# esp_altimeter_evo2.net
KiCad netlist of a schematic drawn in Altium Designer
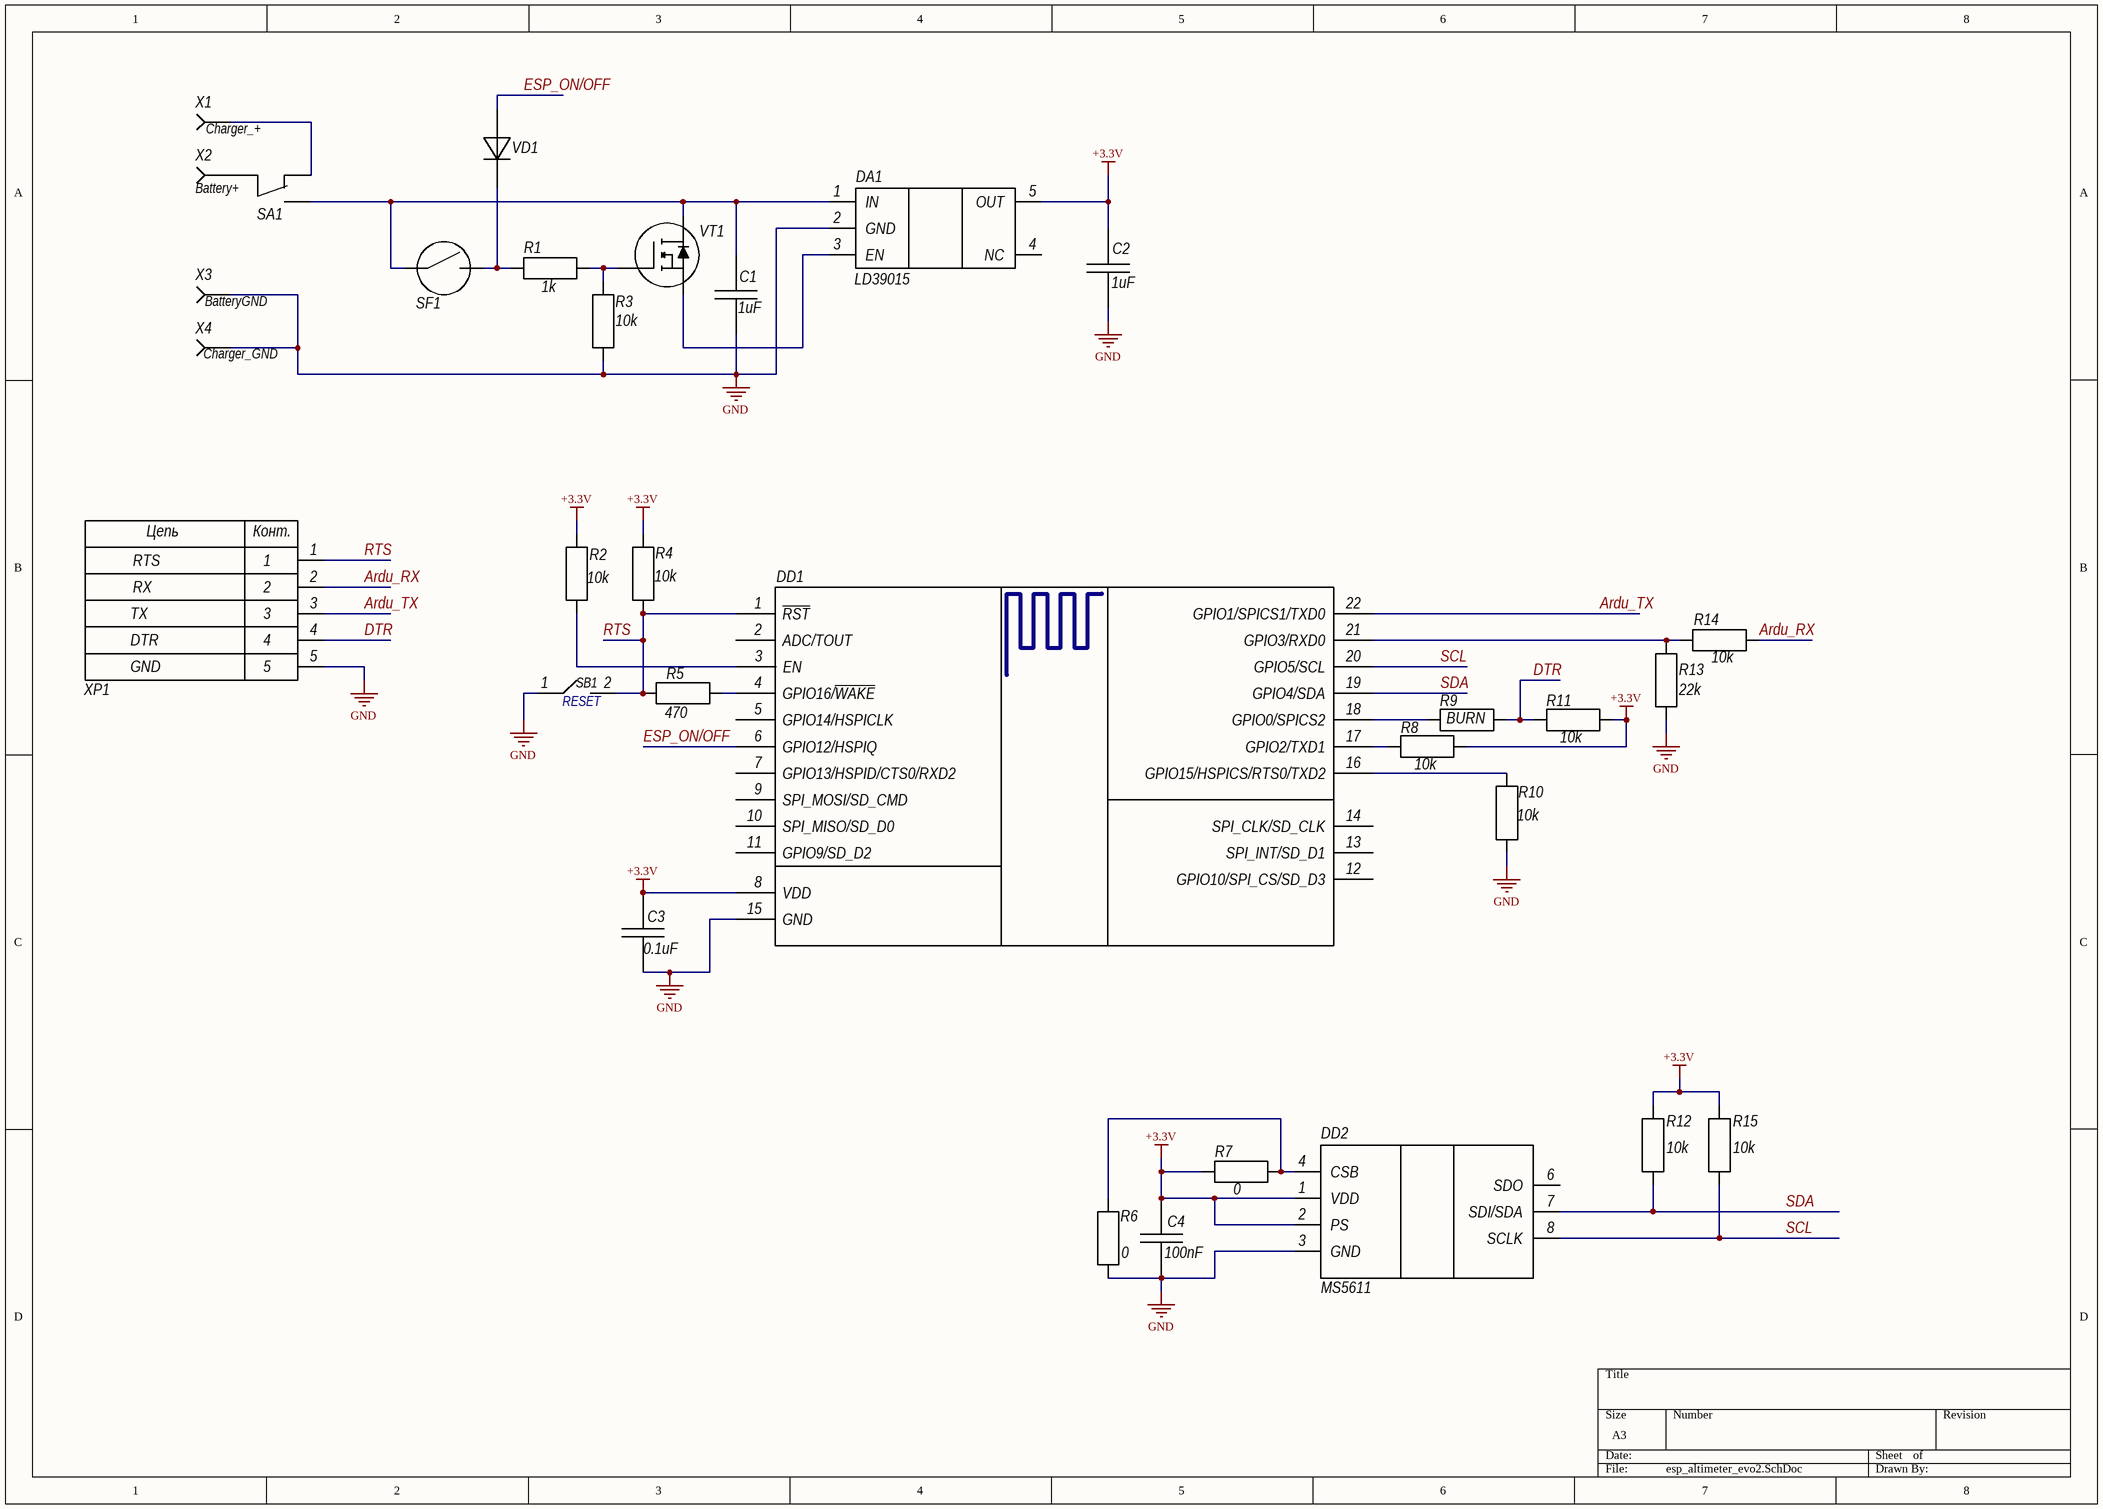
[diagram p0: esp_altimeter_evo2.SchDoc]

(export (version "E")
  (design (tool "Eeschema 10.0.6"))
  (components
    (comp (ref "C1")
      (value "1uF")
      (footprint "CAP EIA 0603")
      (fields (field (name "Comment") "Cap EIA 0603"))
      (libsource (lib "Altium_Capicators_Lib") (part "Cap EIA 0603"))
    )
    (comp (ref "C2")
      (value "1uF")
      (footprint "CAP EIA 0603")
      (fields (field (name "Comment") "Cap EIA 0603"))
      (libsource (lib "Altium_Capicators_Lib") (part "Cap EIA 0603"))
    )
    (comp (ref "C3")
      (value "0.1uF")
      (footprint "CAP EIA 0603")
      (fields (field (name "Comment") "Cap EIA 0603"))
      (libsource (lib "Altium_Capicators_Lib") (part "Cap EIA 0603"))
    )
    (comp (ref "C4")
      (value "100nF")
      (footprint "CAP EIA 0603")
      (fields (field (name "Comment") "Cap EIA 0603"))
      (libsource (lib "Altium_Capicators_Lib") (part "Cap EIA 0603"))
    )
    (comp (ref "DA1")
      (value "LD39015")
      (footprint "SOT23-5L")
      (libsource (lib "Altium_Power_System_Lib") (part "LD39015"))
    )
    (comp (ref "DD1")
      (value "ESP8266 ESP-12E-RU")
      (footprint "ESP8266 ESP-12-E")
      (fields (field (name "MANUFACTURER") "Espressif"))
      (libsource (lib "Altium_Microcontrollers_Lib") (part "ESP8266 ESP-12E-RU"))
    )
    (comp (ref "DD2")
      (value "MS5611")
      (footprint "MS5611")
      (libsource (lib "Altium_Sensors_Lib") (part "MS5611"))
    )
    (comp (ref "R1")
      (value "1k")
      (footprint "RES EIA 0603")
      (fields (field (name "Comment") "Res EIA 0603"))
      (libsource (lib "Altium_Resistors_Lib") (part "Res EIA 0603"))
    )
    (comp (ref "R2")
      (value "10k")
      (footprint "RES EIA 0603")
      (fields (field (name "Comment") "Res EIA 0603"))
      (libsource (lib "Altium_Resistors_Lib") (part "Res EIA 0603"))
    )
    (comp (ref "R3")
      (value "10k")
      (footprint "RES EIA 0603")
      (fields (field (name "Comment") "Res EIA 0603"))
      (libsource (lib "Altium_Resistors_Lib") (part "Res EIA 0603"))
    )
    (comp (ref "R4")
      (value "10k")
      (footprint "RES EIA 0603")
      (fields (field (name "Comment") "Res EIA 0603"))
      (libsource (lib "Altium_Resistors_Lib") (part "Res EIA 0603"))
    )
    (comp (ref "R5")
      (value "470")
      (footprint "RES EIA 0603")
      (fields (field (name "Comment") "Res EIA 0603"))
      (libsource (lib "Altium_Resistors_Lib") (part "Res EIA 0603"))
    )
    (comp (ref "R6")
      (value "0")
      (footprint "RES EIA 0402")
      (fields (field (name "Comment") "Res EIA 0402"))
      (libsource (lib "Altium_Resistors_Lib") (part "Res EIA 0402"))
    )
    (comp (ref "R7")
      (value "0")
      (footprint "RES EIA 0402")
      (fields (field (name "Comment") "Res EIA 0402"))
      (libsource (lib "Altium_Resistors_Lib") (part "Res EIA 0402"))
    )
    (comp (ref "R8")
      (value "10k")
      (footprint "RES EIA 0603")
      (fields (field (name "Comment") "Res EIA 0603"))
      (libsource (lib "Altium_Resistors_Lib") (part "Res EIA 0603"))
    )
    (comp (ref "R9")
      (value "Res EIA 0603")
      (footprint "RES EIA 0603")
      (fields (field (name "NAME") "BURN"))
      (libsource (lib "Altium_Resistors_Lib") (part "Res EIA 0603"))
    )
    (comp (ref "R10")
      (value "10k")
      (footprint "RES EIA 0603")
      (fields (field (name "Comment") "Res EIA 0603"))
      (libsource (lib "Altium_Resistors_Lib") (part "Res EIA 0603"))
    )
    (comp (ref "R11")
      (value "10k")
      (footprint "RES EIA 0603")
      (fields (field (name "Comment") "Res EIA 0603"))
      (libsource (lib "Altium_Resistors_Lib") (part "Res EIA 0603"))
    )
    (comp (ref "R12")
      (value "10k")
      (footprint "RES EIA 0603")
      (fields (field (name "Comment") "Res EIA 0603"))
      (libsource (lib "Altium_Resistors_Lib") (part "Res EIA 0603"))
    )
    (comp (ref "R13")
      (value "22k")
      (footprint "RES EIA 0603")
      (fields (field (name "Comment") "Res EIA 0603"))
      (libsource (lib "Altium_Resistors_Lib") (part "Res EIA 0603"))
    )
    (comp (ref "R14")
      (value "10k")
      (footprint "RES EIA 0603")
      (fields (field (name "Comment") "Res EIA 0603"))
      (libsource (lib "Altium_Resistors_Lib") (part "Res EIA 0603"))
    )
    (comp (ref "R15")
      (value "10k")
      (footprint "RES EIA 0603")
      (fields (field (name "Comment") "Res EIA 0603"))
      (libsource (lib "Altium_Resistors_Lib") (part "Res EIA 0603"))
    )
    (comp (ref "SA1")
      (value "IS-1290")
      (footprint "IS-1290F")
      (libsource (lib "Altium_Switchers_Lib") (part "IS-1290"))
    )
    (comp (ref "SB1")
      (value "RESET")
      (footprint "SB_Pad")
      (libsource (lib "Altium_Connectors_Lib") (part "SB_Pad"))
    )
    (comp (ref "SF1")
      (value "MK23-35-B-2")
      (footprint "MK23-35-B-2")
      (fields (field (name "MANUFACTURER") "MEDER electronic"))
      (libsource (lib "Altium_ElectroMechanics_Lib") (part "MK23-35-B-2"))
    )
    (comp (ref "VD1")
      (value "BAT54HT1G")
      (footprint "SOD-323")
      (description "SCHOTTKY BARRIER DIOD 0.2 AMPERES, 30 VOLTS")
      (libsource (lib "Semiconductors") (part "BAT54HT1G"))
    )
    (comp (ref "VT1")
      (value "IRLML2402PbF")
      (footprint "sot23")
      (description "N-Channel HEXFET  Power MOSFET")
      (fields (field (name "MANUFACTURER") "International Rectifier"))
      (libsource (lib "Altium_Transistors_Lib") (part "IRLML2402PbF"))
    )
    (comp (ref "X1")
      (value "Charger_+")
      (footprint "Surface_Pad")
      (libsource (lib "Altium_Connectors_Lib") (part "Surface_Pad"))
    )
    (comp (ref "X2")
      (value "Battery+")
      (footprint "Surface_Pad")
      (libsource (lib "Altium_Connectors_Lib") (part "Surface_Pad"))
    )
    (comp (ref "X3")
      (value "BatteryGND")
      (footprint "Surface_Pad")
      (libsource (lib "Altium_Connectors_Lib") (part "Surface_Pad"))
    )
    (comp (ref "X4")
      (value "Charger_GND")
      (footprint "Surface_Pad")
      (libsource (lib "Altium_Connectors_Lib") (part "Surface_Pad"))
    )
    (comp (ref "XP1")
      (value "BM05B-SRSS-TB")
      (footprint "BM05B-SRSS-TB")
      (description "5-Pin Angle Connector")
      (fields (field (name "MANUFACTURER") "JST"))
      (libsource (lib "Altium_Connectors_Lib") (part "BM05B-SRSS-TB"))
    )
  )
  (nets
    (net (code "1") (name "+3.3V") (class "Default")
      (node (ref "C2") (pin "2") (pinfunction "2_2") (pintype "passive"))
      (node (ref "C3") (pin "2") (pinfunction "2_2") (pintype "passive"))
      (node (ref "C4") (pin "2") (pinfunction "2_2") (pintype "passive"))
      (node (ref "DA1") (pin "5") (pinfunction "OUT_5") (pintype "passive"))
      (node (ref "DD1") (pin "8") (pinfunction "VDD_8") (pintype "passive"))
      (node (ref "DD2") (pin "1") (pinfunction "VDD_1") (pintype "passive"))
      (node (ref "DD2") (pin "2") (pinfunction "PS_2") (pintype "passive"))
      (node (ref "R11") (pin "2") (pinfunction "2_2") (pintype "passive"))
      (node (ref "R12") (pin "2") (pinfunction "2_2") (pintype "passive"))
      (node (ref "R15") (pin "2") (pinfunction "2_2") (pintype "passive"))
      (node (ref "R2") (pin "2") (pinfunction "2_2") (pintype "passive"))
      (node (ref "R4") (pin "2") (pinfunction "2_2") (pintype "passive"))
      (node (ref "R7") (pin "1") (pinfunction "1_1") (pintype "passive"))
      (node (ref "R8") (pin "2") (pinfunction "2_2") (pintype "passive"))
    )
    (net (code "2") (name "/Ardu_RX") (class "Default")
      (node (ref "R14") (pin "2") (pinfunction "2_2") (pintype "passive"))
      (node (ref "XP1") (pin "2") (pinfunction "2_2") (pintype "passive"))
    )
    (net (code "3") (name "/Ardu_TX") (class "Default")
      (node (ref "DD1") (pin "22") (pinfunction "GPIO1/SPICS1/TXD0_22") (pintype "passive"))
      (node (ref "XP1") (pin "3") (pinfunction "3_3") (pintype "passive"))
    )
    (net (code "4") (name "/DTR") (class "Default")
      (node (ref "R11") (pin "1") (pinfunction "1_1") (pintype "passive"))
      (node (ref "R9") (pin "2") (pinfunction "2_2") (pintype "passive"))
      (node (ref "XP1") (pin "4") (pinfunction "4_4") (pintype "passive"))
    )
    (net (code "5") (name "/ESP_ON{slash}OFF") (class "Default")
      (node (ref "DD1") (pin "6") (pinfunction "GPIO12/HSPIQ_6") (pintype "passive"))
      (node (ref "VD1") (pin "1") (pinfunction "A_1") (pintype "passive"))
    )
    (net (code "6") (name "/RTS") (class "Default")
      (node (ref "DD1") (pin "1") (pinfunction "~{RST}_1") (pintype "passive"))
      (node (ref "R4") (pin "1") (pinfunction "1_1") (pintype "passive"))
      (node (ref "R5") (pin "1") (pinfunction "1_1") (pintype "passive"))
      (node (ref "SB1") (pin "2") (pinfunction "OUT_2") (pintype "passive"))
      (node (ref "XP1") (pin "1") (pinfunction "1_1") (pintype "passive"))
    )
    (net (code "7") (name "/SCL") (class "Default")
      (node (ref "DD1") (pin "20") (pinfunction "GPIO5/SCL_20") (pintype "passive"))
      (node (ref "DD2") (pin "8") (pinfunction "SCLK_8") (pintype "passive"))
      (node (ref "R15") (pin "1") (pinfunction "1_1") (pintype "passive"))
    )
    (net (code "8") (name "/SDA") (class "Default")
      (node (ref "DD1") (pin "19") (pinfunction "GPIO4/SDA_19") (pintype "passive"))
      (node (ref "DD2") (pin "7") (pinfunction "SDI/SDA_7") (pintype "passive"))
      (node (ref "R12") (pin "1") (pinfunction "1_1") (pintype "passive"))
    )
    (net (code "9") (name "GND") (class "Default")
      (node (ref "C1") (pin "1") (pinfunction "1_1") (pintype "passive"))
      (node (ref "C2") (pin "1") (pinfunction "1_1") (pintype "passive"))
      (node (ref "C3") (pin "1") (pinfunction "1_1") (pintype "passive"))
      (node (ref "C4") (pin "1") (pinfunction "1_1") (pintype "passive"))
      (node (ref "DA1") (pin "2") (pinfunction "GND_2") (pintype "passive"))
      (node (ref "DD1") (pin "15") (pinfunction "GND_15") (pintype "passive"))
      (node (ref "DD2") (pin "3") (pinfunction "GND_3") (pintype "passive"))
      (node (ref "R10") (pin "1") (pinfunction "1_1") (pintype "passive"))
      (node (ref "R13") (pin "1") (pinfunction "1_1") (pintype "passive"))
      (node (ref "R3") (pin "1") (pinfunction "1_1") (pintype "passive"))
      (node (ref "R6") (pin "1") (pinfunction "1_1") (pintype "passive"))
      (node (ref "SB1") (pin "1") (pinfunction "OUT_1") (pintype "passive"))
      (node (ref "X3") (pin "1") (pinfunction "1_1") (pintype "passive"))
      (node (ref "X4") (pin "1") (pinfunction "1_1") (pintype "passive"))
      (node (ref "XP1") (pin "5") (pinfunction "5_5") (pintype "passive"))
    )
    (net (code "10") (name "Net-(DA1-EN)") (class "Default")
      (node (ref "DA1") (pin "3") (pinfunction "EN_3") (pintype "passive"))
      (node (ref "VT1") (pin "2") (pinfunction "S_2") (pintype "passive"))
    )
    (net (code "11") (name "Net-(DA1-IN)") (class "Default")
      (node (ref "C1") (pin "2") (pinfunction "2_2") (pintype "passive"))
      (node (ref "DA1") (pin "1") (pinfunction "IN_1") (pintype "passive"))
      (node (ref "SA1") (pin "1") (pintype "passive"))
      (node (ref "SF1") (pin "1") (pinfunction "1_1") (pintype "passive"))
      (node (ref "VT1") (pin "3") (pinfunction "D_3") (pintype "passive"))
    )
    (net (code "12") (name "Net-(DD1-EN)") (class "Default")
      (node (ref "DD1") (pin "3") (pinfunction "EN_3") (pintype "passive"))
      (node (ref "R2") (pin "1") (pinfunction "1_1") (pintype "passive"))
    )
    (net (code "13") (name "Net-(DD1-GPIO0{slash}SPICS2)") (class "Default")
      (node (ref "DD1") (pin "18") (pinfunction "GPIO0/SPICS2_18") (pintype "passive"))
      (node (ref "R9") (pin "1") (pinfunction "1_1") (pintype "passive"))
    )
    (net (code "14") (name "Net-(DD1-GPIO2{slash}TXD1)") (class "Default")
      (node (ref "DD1") (pin "17") (pinfunction "GPIO2/TXD1_17") (pintype "passive"))
      (node (ref "R8") (pin "1") (pinfunction "1_1") (pintype "passive"))
    )
    (net (code "15") (name "Net-(DD1-GPIO3{slash}RXD0)") (class "Default")
      (node (ref "DD1") (pin "21") (pinfunction "GPIO3/RXD0_21") (pintype "passive"))
      (node (ref "R13") (pin "2") (pinfunction "2_2") (pintype "passive"))
      (node (ref "R14") (pin "1") (pinfunction "1_1") (pintype "passive"))
    )
    (net (code "16") (name "Net-(DD1-GPIO15{slash}HSPICS{slash}RTS0{slash}TXD2)") (class "Default")
      (node (ref "DD1") (pin "16") (pinfunction "GPIO15/HSPICS/RTS0/TXD2_16") (pintype "passive"))
      (node (ref "R10") (pin "2") (pinfunction "2_2") (pintype "passive"))
    )
    (net (code "17") (name "Net-(DD1-GPIO16{slash}~{WAKE})") (class "Default")
      (node (ref "DD1") (pin "4") (pinfunction "GPIO16/~{WAKE}_4") (pintype "passive"))
      (node (ref "R5") (pin "2") (pinfunction "2_2") (pintype "passive"))
    )
    (net (code "18") (name "Net-(DD2-CSB-Pad4)") (class "Default")
      (node (ref "DD2") (pin "4") (pinfunction "CSB_4") (pintype "passive"))
      (node (ref "R6") (pin "2") (pinfunction "2_2") (pintype "passive"))
      (node (ref "R7") (pin "2") (pinfunction "2_2") (pintype "passive"))
    )
    (net (code "19") (name "Net-(SA1-Pad2)") (class "Default")
      (node (ref "SA1") (pin "2") (pintype "passive"))
      (node (ref "X2") (pin "1") (pinfunction "1_1") (pintype "passive"))
    )
    (net (code "20") (name "Net-(SA1-Pad3)") (class "Default")
      (node (ref "SA1") (pin "3") (pintype "passive"))
      (node (ref "X1") (pin "1") (pinfunction "1_1") (pintype "passive"))
    )
    (net (code "21") (name "Net-(VD1-K)") (class "Default")
      (node (ref "R1") (pin "1") (pinfunction "1_1") (pintype "passive"))
      (node (ref "SF1") (pin "2") (pinfunction "2_2") (pintype "passive"))
      (node (ref "VD1") (pin "2") (pinfunction "K_2") (pintype "passive"))
    )
    (net (code "22") (name "Net-(VT1-G)") (class "Default")
      (node (ref "R1") (pin "2") (pinfunction "2_2") (pintype "passive"))
      (node (ref "R3") (pin "2") (pinfunction "2_2") (pintype "passive"))
      (node (ref "VT1") (pin "1") (pinfunction "G_1") (pintype "passive"))
    )
    (net (code "23") (name "unconnected-(DA1-NC-Pad4)") (class "Default")
      (node (ref "DA1") (pin "4") (pinfunction "NC_4") (pintype "passive"))
    )
    (net (code "24") (name "unconnected-(DD1-ADC{slash}TOUT-Pad2)") (class "Default")
      (node (ref "DD1") (pin "2") (pinfunction "ADC/TOUT_2") (pintype "passive"))
    )
    (net (code "25") (name "unconnected-(DD1-GPIO9{slash}SD_D2-Pad11)") (class "Default")
      (node (ref "DD1") (pin "11") (pinfunction "GPIO9/SD_D2_11") (pintype "passive"))
    )
    (net (code "26") (name "unconnected-(DD1-GPIO10{slash}SPI_CS{slash}SD_D3-Pad12)") (class "Default")
      (node (ref "DD1") (pin "12") (pinfunction "GPIO10/SPI_CS/SD_D3_12") (pintype "passive"))
    )
    (net (code "27") (name "unconnected-(DD1-GPIO13{slash}HSPID{slash}CTS0{slash}RXD2-Pad7)") (class "Default")
      (node (ref "DD1") (pin "7") (pinfunction "GPIO13/HSPID/CTS0/RXD2_7") (pintype "passive"))
    )
    (net (code "28") (name "unconnected-(DD1-GPIO14{slash}HSPICLK-Pad5)") (class "Default")
      (node (ref "DD1") (pin "5") (pinfunction "GPIO14/HSPICLK_5") (pintype "passive"))
    )
    (net (code "29") (name "unconnected-(DD1-SPI_CLK{slash}SD_CLK-Pad14)") (class "Default")
      (node (ref "DD1") (pin "14") (pinfunction "SPI_CLK/SD_CLK_14") (pintype "passive"))
    )
    (net (code "30") (name "unconnected-(DD1-SPI_INT{slash}SD_D1-Pad13)") (class "Default")
      (node (ref "DD1") (pin "13") (pinfunction "SPI_INT/SD_D1_13") (pintype "passive"))
    )
    (net (code "31") (name "unconnected-(DD1-SPI_MISO{slash}SD_D0-Pad10)") (class "Default")
      (node (ref "DD1") (pin "10") (pinfunction "SPI_MISO/SD_D0_10") (pintype "passive"))
    )
    (net (code "32") (name "unconnected-(DD1-SPI_MOSI{slash}SD_CMD-Pad9)") (class "Default")
      (node (ref "DD1") (pin "9") (pinfunction "SPI_MOSI/SD_CMD_9") (pintype "passive"))
    )
    (net (code "33") (name "unconnected-(DD2-CSB-Pad5)") (class "Default")
      (node (ref "DD2") (pin "5") (pinfunction "CSB_5") (pintype "passive"))
    )
    (net (code "34") (name "unconnected-(DD2-SDO-Pad6)") (class "Default")
      (node (ref "DD2") (pin "6") (pinfunction "SDO_6") (pintype "passive"))
    )
  )
)
